# driver_V1_5.net
KiCad netlist of a schematic drawn in Altium Designer
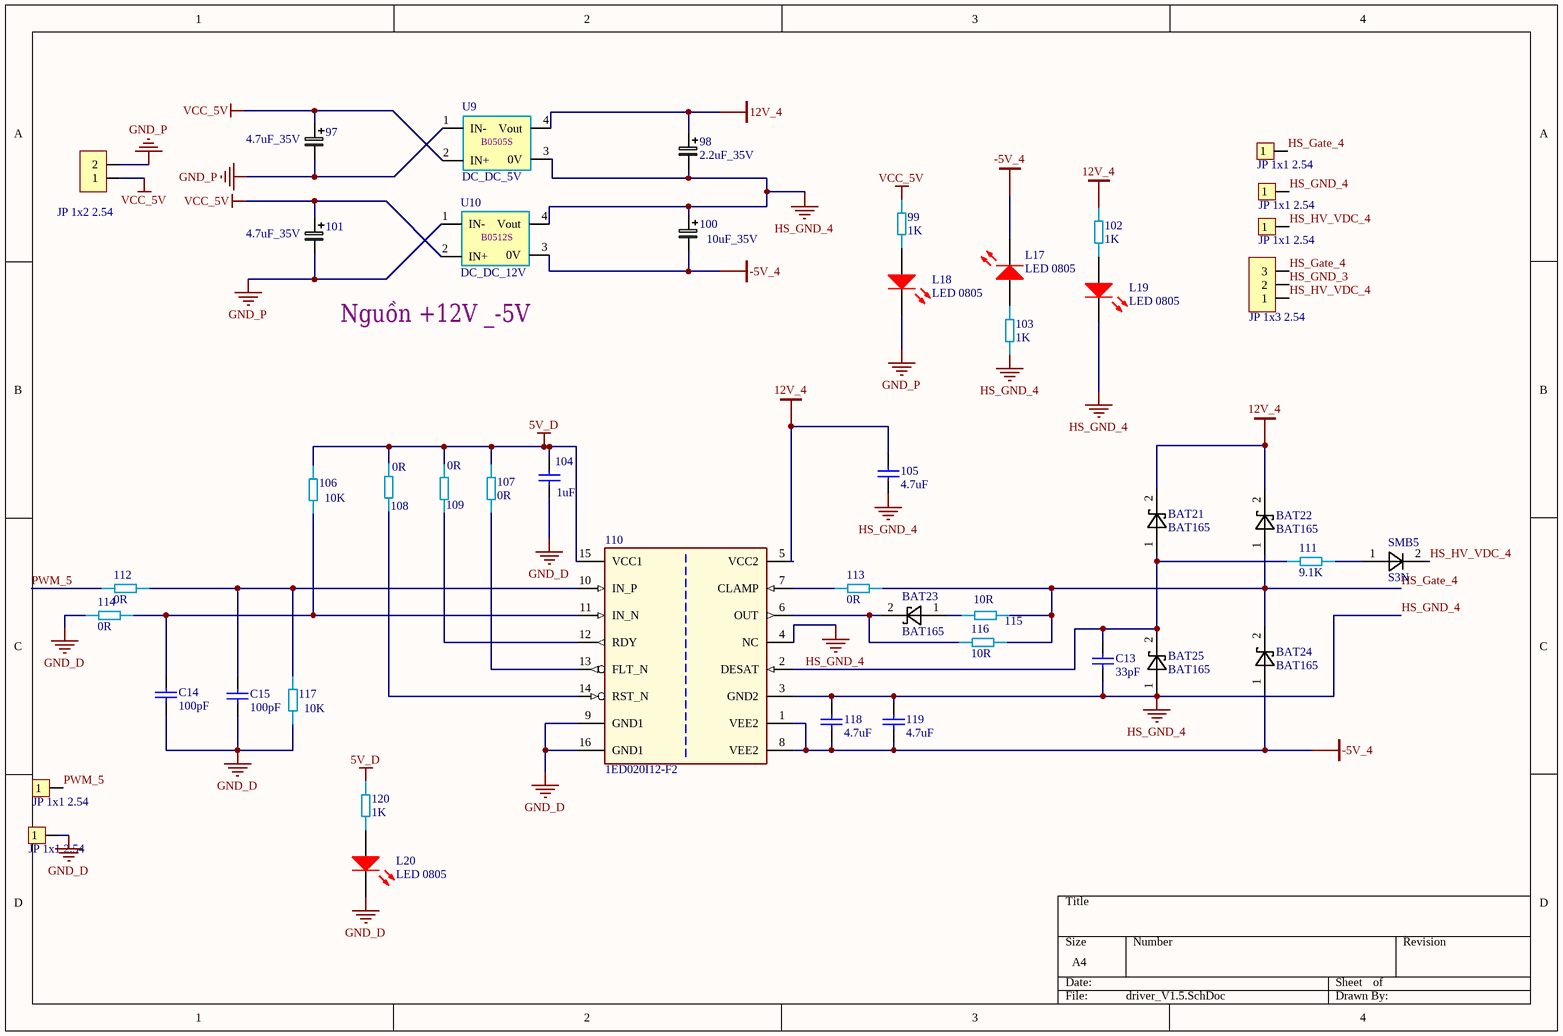
[diagram p0: driver_V1.5.SchDoc]

(export (version "E")
  (design (tool "Eeschema 10.0.6"))
  (components
    (comp (ref "97")
      (value "4.7uF_35V")
      (footprint "tu_4x5.4mm")
      (description "capacitor_electric")
      (libsource (lib "labari_altium1") (part "capacitor_electric"))
    )
    (comp (ref "98")
      (value "2.2uF_35V")
      (footprint "tu_4x5.4mm")
      (description "capacitor_electric")
      (libsource (lib "labari_altium1") (part "capacitor_electric"))
    )
    (comp (ref "99")
      (value "1K")
      (footprint "RES1206")
      (libsource (lib "labari_altium1") (part "311-0.0GRTR-ND"))
    )
    (comp (ref "100")
      (value "10uF_35V")
      (footprint "tu_4x5.4mm")
      (description "capacitor_electric")
      (libsource (lib "labari_altium1") (part "capacitor_electric"))
    )
    (comp (ref "101")
      (value "4.7uF_35V")
      (footprint "tu_4x5.4mm")
      (description "capacitor_electric")
      (libsource (lib "labari_altium1") (part "capacitor_electric"))
    )
    (comp (ref "102")
      (value "1K")
      (footprint "RES1206")
      (libsource (lib "labari_altium1") (part "311-0.0GRTR-ND"))
    )
    (comp (ref "103")
      (value "1K")
      (footprint "RES1206")
      (libsource (lib "labari_altium1") (part "311-0.0GRTR-ND"))
    )
    (comp (ref "104")
      (value "1uF")
      (footprint "Tu 0805_N")
      (libsource (lib "labari_altium1") (part "cap_0805"))
    )
    (comp (ref "105")
      (value "4.7uF")
      (footprint "tu 1206_N")
      (libsource (lib "labari_altium1") (part "cap_1210"))
    )
    (comp (ref "106")
      (value "10K")
      (footprint "RES1206")
      (libsource (lib "labari_altium1") (part "311-0.0GRTR-ND"))
    )
    (comp (ref "107")
      (value "0R")
      (footprint "RES1206")
      (libsource (lib "labari_altium1") (part "311-0.0GRTR-ND"))
    )
    (comp (ref "108")
      (value "0R")
      (footprint "RES1206")
      (libsource (lib "labari_altium1") (part "311-0.0GRTR-ND"))
    )
    (comp (ref "109")
      (value "0R")
      (footprint "RES1206")
      (libsource (lib "labari_altium1") (part "311-0.0GRTR-ND"))
    )
    (comp (ref "110")
      (value "1ED020I12-F2")
      (footprint "SOIC127P1028X264-16N-1")
      (description "Single IGBT Driver IC")
      (fields (field (name "MANUFACTURER") "Infineon Technologies"))
      (libsource (lib "labari_altium1") (part "1ED020I12-F2"))
    )
    (comp (ref "111")
      (value "9.1K")
      (footprint "RES_2512")
      (libsource (lib "labari_altium1") (part "311-0.0GRTR-ND"))
    )
    (comp (ref "112")
      (value "0R")
      (footprint "RES1206")
      (libsource (lib "labari_altium1") (part "311-0.0GRTR-ND"))
    )
    (comp (ref "113")
      (value "0R")
      (footprint "RES_2512")
      (libsource (lib "labari_altium1") (part "311-0.0GRTR-ND"))
    )
    (comp (ref "114")
      (value "0R")
      (footprint "RES1206")
      (libsource (lib "labari_altium1") (part "311-0.0GRTR-ND"))
    )
    (comp (ref "115")
      (value "10R")
      (footprint "RES_2512")
      (libsource (lib "labari_altium1") (part "311-0.0GRTR-ND"))
    )
    (comp (ref "116")
      (value "10R")
      (footprint "RES_2512")
      (libsource (lib "labari_altium1") (part "311-0.0GRTR-ND"))
    )
    (comp (ref "117")
      (value "10K")
      (footprint "RES1206")
      (libsource (lib "labari_altium1") (part "311-0.0GRTR-ND"))
    )
    (comp (ref "118")
      (value "4.7uF")
      (footprint "tu 1206_N")
      (libsource (lib "labari_altium1") (part "cap_1210"))
    )
    (comp (ref "119")
      (value "4.7uF")
      (footprint "tu 1206_N")
      (libsource (lib "labari_altium1") (part "cap_1210"))
    )
    (comp (ref "120")
      (value "1K")
      (footprint "RES1206")
      (libsource (lib "labari_altium1") (part "311-0.0GRTR-ND"))
    )
    (comp (ref "BAT21") (value "BAT165") (footprint "SMB") (libsource (lib "labari_altium1") (part "BAT165")))
    (comp (ref "BAT22") (value "BAT165") (footprint "SMB") (libsource (lib "labari_altium1") (part "BAT165")))
    (comp (ref "BAT23") (value "BAT165") (footprint "SMB") (libsource (lib "labari_altium1") (part "BAT165")))
    (comp (ref "BAT24") (value "BAT165") (footprint "SMB") (libsource (lib "labari_altium1") (part "BAT165")))
    (comp (ref "BAT25") (value "BAT165") (footprint "SMB") (libsource (lib "labari_altium1") (part "BAT165")))
    (comp (ref "C13")
      (value "33pF")
      (footprint "Tu 0805_N")
      (libsource (lib "labari_altium1") (part "cap_0805"))
    )
    (comp (ref "C14")
      (value "100pF")
      (footprint "Tu 0805_N")
      (libsource (lib "labari_altium1") (part "cap_0805"))
    )
    (comp (ref "C15")
      (value "100pF")
      (footprint "Tu 0805_N")
      (libsource (lib "labari_altium1") (part "cap_0805"))
    )
    (comp (ref "JP30")
      (value "JP 1x1 2.54")
      (footprint "test_point")
      (description "Cắm")
      (libsource (lib "labari_altium1") (part "JP 1x1 2.54 Duc Thang"))
    )
    (comp (ref "JP31")
      (value "JP 1x2 2.54")
      (footprint "JP 1x2 DT_n")
      (description "Cắm")
      (libsource (lib "labari_altium1") (part "JP 1x2 2.54 Duc Thang"))
    )
    (comp (ref "JP32")
      (value "JP 1x1 2.54")
      (footprint "test_point")
      (description "Cắm")
      (libsource (lib "labari_altium1") (part "JP 1x1 2.54 Duc Thang"))
    )
    (comp (ref "JP33")
      (value "JP 1x1 2.54")
      (footprint "test_point")
      (description "Cắm")
      (libsource (lib "labari_altium1") (part "JP 1x1 2.54 Duc Thang"))
    )
    (comp (ref "JP34")
      (value "JP 1x3 2.54")
      (footprint "XH2.54M-3")
      (description "Cắm")
      (libsource (lib "labari_altium1") (part "JP 1x3 2.54 Duc Cong"))
    )
    (comp (ref "JP35")
      (value "JP 1x1 2.54")
      (footprint "test_point")
      (description "Cắm")
      (libsource (lib "labari_altium1") (part "JP 1x1 2.54 Duc Thang"))
    )
    (comp (ref "JP36")
      (value "JP 1x1 2.54")
      (footprint "test_point")
      (description "Cắm")
      (libsource (lib "labari_altium1") (part "JP 1x1 2.54 Duc Thang"))
    )
    (comp (ref "L17")
      (value "LED 0805")
      (footprint "LED-0805-Red")
      (description "Dán")
      (libsource (lib "labari_altium1") (part "LED 0805 Do"))
    )
    (comp (ref "L18")
      (value "LED 0805")
      (footprint "LED-0805-Red")
      (description "Dán")
      (libsource (lib "labari_altium1") (part "LED 0805 Do"))
    )
    (comp (ref "L19")
      (value "LED 0805")
      (footprint "LED-0805-Red")
      (description "Dán")
      (libsource (lib "labari_altium1") (part "LED 0805 Do"))
    )
    (comp (ref "L20")
      (value "LED 0805")
      (footprint "LED-0805-Red")
      (description "Dán")
      (libsource (lib "labari_altium1") (part "LED 0805 Do"))
    )
    (comp (ref "SMB5") (value "S3N") (footprint "SMB") (libsource (lib "labari_altium1") (part "S3A-S3N")))
    (comp (ref "U9")
      (value "DC_DC_5V")
      (footprint "B0505S/D-1W")
      (libsource (lib "labari_altium1") (part "DC_DC_5v"))
    )
    (comp (ref "U10")
      (value "DC_DC_12V")
      (footprint "B0512S/D-1W")
      (libsource (lib "labari_altium1") (part "DC_DC_12v"))
    )
  )
  (nets
    (net (code "1") (name "-5V_4") (class "Default")
      (node (ref "100") (pin "2") (pinfunction "2_2") (pintype "passive"))
      (node (ref "110") (pin "1") (pinfunction "VEE2_1") (pintype "power_in"))
      (node (ref "110") (pin "8") (pinfunction "VEE2_8") (pintype "power_in"))
      (node (ref "118") (pin "1") (pinfunction "1_1") (pintype "passive"))
      (node (ref "119") (pin "1") (pinfunction "1_1") (pintype "passive"))
      (node (ref "BAT24") (pin "1") (pinfunction "1_1") (pintype "passive"))
      (node (ref "L17") (pin "2") (pinfunction "K_2") (pintype "passive"))
      (node (ref "U10") (pin "3") (pinfunction "0V_3") (pintype "passive"))
    )
    (net (code "2") (name "/HS_GND_3") (class "Default")
      (node (ref "JP34") (pin "2") (pinfunction "2_2") (pintype "passive"))
    )
    (net (code "3") (name "/HS_Gate_4") (class "Default")
      (node (ref "113") (pin "2") (pinfunction "2_2") (pintype "passive"))
      (node (ref "115") (pin "2") (pinfunction "2_2") (pintype "passive"))
      (node (ref "116") (pin "2") (pinfunction "2_2") (pintype "passive"))
      (node (ref "BAT22") (pin "1") (pinfunction "1_1") (pintype "passive"))
      (node (ref "BAT24") (pin "2") (pinfunction "2_2") (pintype "passive"))
      (node (ref "JP30") (pin "1") (pinfunction "1_1") (pintype "passive"))
      (node (ref "JP34") (pin "3") (pinfunction "3_3") (pintype "passive"))
    )
    (net (code "4") (name "/HS_HV_VDC_4") (class "Default")
      (node (ref "JP33") (pin "1") (pinfunction "1_1") (pintype "passive"))
      (node (ref "JP34") (pin "1") (pinfunction "1_1") (pintype "passive"))
      (node (ref "SMB5") (pin "2") (pinfunction "2_2") (pintype "passive"))
    )
    (net (code "5") (name "/PWM_5") (class "Default")
      (node (ref "112") (pin "2") (pinfunction "2_2") (pintype "passive"))
      (node (ref "JP35") (pin "1") (pinfunction "1_1") (pintype "passive"))
    )
    (net (code "6") (name "5V_D") (class "Default")
      (node (ref "104") (pin "2") (pinfunction "2_2") (pintype "passive"))
      (node (ref "106") (pin "2") (pinfunction "2_2") (pintype "passive"))
      (node (ref "107") (pin "1") (pinfunction "1_1") (pintype "passive"))
      (node (ref "108") (pin "2") (pinfunction "2_2") (pintype "passive"))
      (node (ref "109") (pin "1") (pinfunction "1_1") (pintype "passive"))
      (node (ref "110") (pin "15") (pinfunction "VCC1_15") (pintype "power_in"))
      (node (ref "120") (pin "1") (pinfunction "1_1") (pintype "passive"))
    )
    (net (code "7") (name "12V_4") (class "Default")
      (node (ref "102") (pin "1") (pinfunction "1_1") (pintype "passive"))
      (node (ref "105") (pin "2") (pinfunction "2_2") (pintype "passive"))
      (node (ref "110") (pin "5") (pinfunction "VCC2_5") (pintype "power_in"))
      (node (ref "98") (pin "1") (pinfunction "1_1") (pintype "passive"))
      (node (ref "BAT21") (pin "2") (pinfunction "2_2") (pintype "passive"))
      (node (ref "BAT22") (pin "2") (pinfunction "2_2") (pintype "passive"))
      (node (ref "U9") (pin "4") (pinfunction "Vout_4") (pintype "passive"))
    )
    (net (code "8") (name "GND_D") (class "Default")
      (node (ref "104") (pin "1") (pinfunction "1_1") (pintype "passive"))
      (node (ref "110") (pin "16") (pinfunction "GND1_16") (pintype "power_in"))
      (node (ref "110") (pin "9") (pinfunction "GND1_9") (pintype "power_in"))
      (node (ref "114") (pin "2") (pinfunction "2_2") (pintype "passive"))
      (node (ref "117") (pin "1") (pinfunction "1_1") (pintype "passive"))
      (node (ref "C14") (pin "1") (pinfunction "1_1") (pintype "passive"))
      (node (ref "C15") (pin "1") (pinfunction "1_1") (pintype "passive"))
      (node (ref "JP36") (pin "1") (pinfunction "1_1") (pintype "passive"))
      (node (ref "L20") (pin "2") (pinfunction "K_2") (pintype "passive"))
    )
    (net (code "9") (name "GND_P") (class "Default")
      (node (ref "101") (pin "2") (pinfunction "2_2") (pintype "passive"))
      (node (ref "97") (pin "2") (pinfunction "2_2") (pintype "passive"))
      (node (ref "JP31") (pin "2") (pinfunction "2_2") (pintype "passive"))
      (node (ref "L18") (pin "2") (pinfunction "K_2") (pintype "passive"))
      (node (ref "U10") (pin "1") (pinfunction "IN-_1") (pintype "passive"))
      (node (ref "U9") (pin "1") (pinfunction "IN-_1") (pintype "passive"))
    )
    (net (code "10") (name "HS_GND_4") (class "Default")
      (node (ref "100") (pin "1") (pinfunction "1_1") (pintype "passive"))
      (node (ref "103") (pin "2") (pinfunction "2_2") (pintype "passive"))
      (node (ref "105") (pin "1") (pinfunction "1_1") (pintype "passive"))
      (node (ref "110") (pin "3") (pinfunction "GND2_3") (pintype "power_in"))
      (node (ref "110") (pin "4") (pinfunction "NC_4") (pintype "passive"))
      (node (ref "118") (pin "2") (pinfunction "2_2") (pintype "passive"))
      (node (ref "119") (pin "2") (pinfunction "2_2") (pintype "passive"))
      (node (ref "98") (pin "2") (pinfunction "2_2") (pintype "passive"))
      (node (ref "BAT25") (pin "1") (pinfunction "1_1") (pintype "passive"))
      (node (ref "C13") (pin "1") (pinfunction "1_1") (pintype "passive"))
      (node (ref "JP32") (pin "1") (pinfunction "1_1") (pintype "passive"))
      (node (ref "L19") (pin "2") (pinfunction "K_2") (pintype "passive"))
      (node (ref "U10") (pin "4") (pinfunction "Vout_4") (pintype "passive"))
      (node (ref "U9") (pin "3") (pinfunction "0V_3") (pintype "passive"))
    )
    (net (code "11") (name "Net-(110-CLAMP)") (class "Default")
      (node (ref "110") (pin "7") (pinfunction "CLAMP_7") (pintype "input"))
      (node (ref "113") (pin "1") (pinfunction "1_1") (pintype "passive"))
    )
    (net (code "12") (name "Net-(110-DESAT)") (class "Default")
      (node (ref "110") (pin "2") (pinfunction "DESAT_2") (pintype "input"))
      (node (ref "111") (pin "1") (pinfunction "1_1") (pintype "passive"))
      (node (ref "BAT21") (pin "1") (pinfunction "1_1") (pintype "passive"))
      (node (ref "BAT25") (pin "2") (pinfunction "2_2") (pintype "passive"))
      (node (ref "C13") (pin "2") (pinfunction "2_2") (pintype "passive"))
    )
    (net (code "13") (name "Net-(110-FLT_N)") (class "Default")
      (node (ref "107") (pin "2") (pinfunction "2_2") (pintype "passive"))
      (node (ref "110") (pin "13") (pinfunction "FLT_N_13") (pintype "output"))
    )
    (net (code "14") (name "Net-(110-IN_N)") (class "Default")
      (node (ref "106") (pin "1") (pinfunction "1_1") (pintype "passive"))
      (node (ref "110") (pin "11") (pinfunction "IN_N_11") (pintype "input"))
      (node (ref "114") (pin "1") (pinfunction "1_1") (pintype "passive"))
      (node (ref "C14") (pin "2") (pinfunction "2_2") (pintype "passive"))
    )
    (net (code "15") (name "Net-(110-IN_P)") (class "Default")
      (node (ref "110") (pin "10") (pinfunction "IN_P_10") (pintype "input"))
      (node (ref "112") (pin "1") (pinfunction "1_1") (pintype "passive"))
      (node (ref "117") (pin "2") (pinfunction "2_2") (pintype "passive"))
      (node (ref "C15") (pin "2") (pinfunction "2_2") (pintype "passive"))
    )
    (net (code "16") (name "Net-(110-OUT)") (class "Default")
      (node (ref "110") (pin "6") (pinfunction "OUT_6") (pintype "output"))
      (node (ref "116") (pin "1") (pinfunction "1_1") (pintype "passive"))
      (node (ref "BAT23") (pin "2") (pinfunction "2_2") (pintype "passive"))
    )
    (net (code "17") (name "Net-(110-RDY)") (class "Default")
      (node (ref "109") (pin "2") (pinfunction "2_2") (pintype "passive"))
      (node (ref "110") (pin "12") (pinfunction "RDY_12") (pintype "output"))
    )
    (net (code "18") (name "Net-(110-RST_N)") (class "Default")
      (node (ref "108") (pin "1") (pinfunction "1_1") (pintype "passive"))
      (node (ref "110") (pin "14") (pinfunction "RST_N_14") (pintype "input"))
    )
    (net (code "19") (name "Net-(111-Pad2)") (class "Default")
      (node (ref "111") (pin "2") (pinfunction "2_2") (pintype "passive"))
      (node (ref "SMB5") (pin "1") (pinfunction "1_1") (pintype "passive"))
    )
    (net (code "20") (name "Net-(115-Pad1)") (class "Default")
      (node (ref "115") (pin "1") (pinfunction "1_1") (pintype "passive"))
      (node (ref "BAT23") (pin "1") (pinfunction "1_1") (pintype "passive"))
    )
    (net (code "21") (name "Net-(L17-A)") (class "Default")
      (node (ref "103") (pin "1") (pinfunction "1_1") (pintype "passive"))
      (node (ref "L17") (pin "1") (pinfunction "A_1") (pintype "passive"))
    )
    (net (code "22") (name "Net-(L18-A)") (class "Default")
      (node (ref "99") (pin "2") (pinfunction "2_2") (pintype "passive"))
      (node (ref "L18") (pin "1") (pinfunction "A_1") (pintype "passive"))
    )
    (net (code "23") (name "Net-(L19-A)") (class "Default")
      (node (ref "102") (pin "2") (pinfunction "2_2") (pintype "passive"))
      (node (ref "L19") (pin "1") (pinfunction "A_1") (pintype "passive"))
    )
    (net (code "24") (name "Net-(L20-A)") (class "Default")
      (node (ref "120") (pin "2") (pinfunction "2_2") (pintype "passive"))
      (node (ref "L20") (pin "1") (pinfunction "A_1") (pintype "passive"))
    )
    (net (code "25") (name "VCC_5V") (class "Default")
      (node (ref "101") (pin "1") (pinfunction "1_1") (pintype "passive"))
      (node (ref "97") (pin "1") (pinfunction "1_1") (pintype "passive"))
      (node (ref "99") (pin "1") (pinfunction "1_1") (pintype "passive"))
      (node (ref "JP31") (pin "1") (pinfunction "1_1") (pintype "passive"))
      (node (ref "U10") (pin "2") (pinfunction "IN+_2") (pintype "passive"))
      (node (ref "U9") (pin "2") (pinfunction "IN+_2") (pintype "passive"))
    )
  )
)
